# ESPBoard.net
KiCad netlist of a schematic drawn in Altium Designer
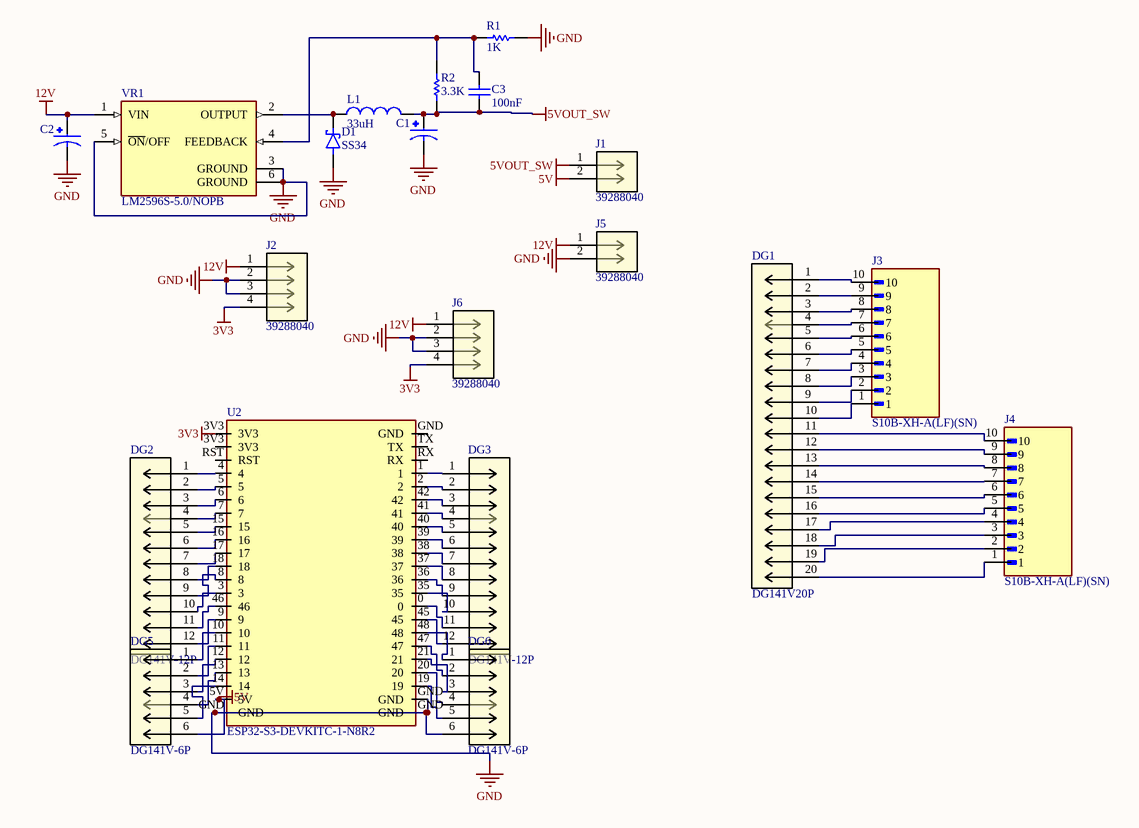
[diagram p0: ESPBoard.SchDoc]

(export (version "E")
  (design (tool "Eeschema 10.0.6"))
  (components
    (comp (ref "C1")
      (value "EEUFR1V101B")
      (footprint "220uF")
      (description "AL LYTIC, RADIAL, 35VDC, 100UF")
      (fields (field (name "MF") "Panasonic"))
      (libsource (lib "Schlib1") (part "EEUFR1V101B"))
    )
    (comp (ref "C2")
      (value "EEUFR1V101B")
      (footprint "100uF")
      (description "AL LYTIC, RADIAL, 35VDC, 100UF")
      (fields (field (name "MF") "Panasonic"))
      (libsource (lib "") (part "EEUFR1V101B_1"))
    )
    (comp (ref "C3")
      (value "100nF")
      (footprint "CAP0805R")
      (description "Capacitor")
      (libsource (lib "Simulation Generic Components") (part "Capacitor"))
    )
    (comp (ref "D1")
      (value "SS34")
      (footprint "DIOM7959X265N")
      (description "Diode Schottky 40 V 3A Surface Mount SMC (DO-214AB)")
      (fields (field (name "MF") "onsemi"))
      (libsource (lib "Schlib1") (part "SS34"))
    )
    (comp (ref "DG1")
      (value "DG141V20P")
      (footprint "141V-20P")
      (libsource (lib "Schlib1") (part "DG141V-20P"))
    )
    (comp (ref "DG2") (value "DG141V-12P") (footprint "141V-12P") (libsource (lib "") (part "DG141V-12P_1")))
    (comp (ref "DG3")
      (value "DG141V-12P")
      (footprint "141V-12P")
      (libsource (lib "Schlib1") (part "DG141V-12P"))
    )
    (comp (ref "DG5")
      (value "DG141V-6P")
      (footprint "141V-6P")
      (libsource (lib "Schlib1") (part "DG141V-6P"))
    )
    (comp (ref "DG6") (value "DG141V-6P") (footprint "141V-6P") (libsource (lib "") (part "DG141V-6P_1")))
    (comp (ref "J1")
      (value "39288040")
      (footprint "5566-02_MOL")
      (fields (field (name "COPYRIGHT") "Copyright (C) 2025 Ultra Librarian. All rights reserved."))
      (libsource (lib "Schlib1") (part "5566-02A"))
    )
    (comp (ref "J2")
      (value "39288040")
      (footprint "5566-04_MOL")
      (fields (field (name "COPYRIGHT") "Copyright (C) 2025 Ultra Librarian. All rights reserved."))
      (libsource (lib "Schlib1") (part "5566-04A"))
    )
    (comp (ref "J3")
      (value "S10B-XH-A(LF)(SN)")
      (footprint "JST_S10B-XH-A(LF)(SN)")
      (libsource (lib "Schlib1") (part "S10B-XH-A(LF)(SN)"))
    )
    (comp (ref "J4")
      (value "S10B-XH-A(LF)(SN)")
      (footprint "JST_S10B-XH-A(LF)(SN)")
      (libsource (lib "Schlib1") (part "S10B-XH-A(LF)(SN)"))
    )
    (comp (ref "J5")
      (value "39288040")
      (footprint "5566-02_MOL")
      (fields (field (name "COPYRIGHT") "Copyright (C) 2025 Ultra Librarian. All rights reserved."))
      (libsource (lib "Schlib1") (part "5566-02A"))
    )
    (comp (ref "J6")
      (value "39288040")
      (footprint "5566-04_MOL")
      (fields (field (name "COPYRIGHT") "Copyright (C) 2025 Ultra Librarian. All rights reserved."))
      (libsource (lib "Schlib1") (part "5566-04A"))
    )
    (comp (ref "L1")
      (value "33uH")
      (footprint "SC1280S-33uH")
      (description "Inductor")
      (libsource (lib "Simulation Generic Components") (part "Inductor"))
    )
    (comp (ref "R1")
      (value "1K")
      (footprint "RES0805W")
      (description "Resistor")
      (libsource (lib "Simulation Generic Components") (part "Resistor"))
    )
    (comp (ref "R2")
      (value "3.3K")
      (footprint "RES0805W")
      (description "Resistor")
      (libsource (lib "Simulation Generic Components") (part "Resistor"))
    )
    (comp (ref "U2")
      (value "ESP32-S3-DEVKITC-1-N8R2")
      (footprint "ESP32-S3-DEVKITC-1")
      (fields (field (name "MF") "Espressif Systems"))
      (libsource (lib "Schlib1") (part "ESP32-S3-DEVKITC-1-N8R2"))
    )
    (comp (ref "VR1")
      (value "LM2596S-5.0/NOPB")
      (footprint "VREG_LM2596S-5.0/NOPB")
      (description "SIMPLE SWITCHERÂ® 4.5V to 40V, 3A Low Component Count Step-Down Regulator 5-DDPAK/TO-263")
      (fields (field (name "MF") "Texas Instruments") (field (name "MP") "LM2596S-5.0"))
      (libsource (lib "Schlib1") (part "LM2596S-5.0/NOPB"))
    )
  )
  (nets
    (net (code "1") (name "3V3") (class "Default")
      (node (ref "J2") (pin "4") (pinfunction "4_4") (pintype "passive"))
      (node (ref "J6") (pin "4") (pinfunction "4_4") (pintype "passive"))
      (node (ref "U2") (pin "3V3") (pinfunction "3V3_3V3") (pintype "passive"))
    )
    (net (code "2") (name "5V") (class "Default")
      (node (ref "DG5") (pin "6") (pinfunction "6_6") (pintype "passive"))
      (node (ref "J1") (pin "2") (pinfunction "2_2") (pintype "passive"))
      (node (ref "U2") (pin "5V") (pinfunction "5V_5V") (pintype "passive"))
    )
    (net (code "3") (name "5VOUT_SW") (class "Default")
      (node (ref "C1") (pin "P") (pinfunction "P_P") (pintype "passive"))
      (node (ref "C3") (pin "1") (pinfunction "1_1") (pintype "passive"))
      (node (ref "J1") (pin "1") (pinfunction "1_1") (pintype "passive"))
      (node (ref "L1") (pin "2") (pinfunction "2_2") (pintype "passive"))
      (node (ref "R2") (pin "1") (pinfunction "1_1") (pintype "passive"))
    )
    (net (code "4") (name "12V") (class "Default")
      (node (ref "C2") (pin "P") (pinfunction "P_P") (pintype "passive"))
      (node (ref "J2") (pin "1") (pinfunction "1_1") (pintype "passive"))
      (node (ref "J5") (pin "1") (pinfunction "1_1") (pintype "passive"))
      (node (ref "J6") (pin "1") (pinfunction "1_1") (pintype "passive"))
      (node (ref "VR1") (pin "1") (pinfunction "VIN_1") (pintype "input"))
    )
    (net (code "5") (name "GND") (class "Default")
      (node (ref "C1") (pin "N") (pinfunction "N_N") (pintype "passive"))
      (node (ref "C2") (pin "N") (pinfunction "N_N") (pintype "passive"))
      (node (ref "D1") (pin "A") (pinfunction "A_A") (pintype "passive"))
      (node (ref "DG6") (pin "6") (pinfunction "6_6") (pintype "passive"))
      (node (ref "J2") (pin "2") (pinfunction "2_2") (pintype "passive"))
      (node (ref "J2") (pin "3") (pinfunction "3_3") (pintype "passive"))
      (node (ref "J5") (pin "2") (pinfunction "2_2") (pintype "passive"))
      (node (ref "J6") (pin "2") (pinfunction "2_2") (pintype "passive"))
      (node (ref "J6") (pin "3") (pinfunction "3_3") (pintype "passive"))
      (node (ref "R1") (pin "1") (pinfunction "1_1") (pintype "passive"))
      (node (ref "U2") (pin "GND") (pinfunction "GND_GND") (pintype "passive"))
      (node (ref "VR1") (pin "3") (pinfunction "GROUND_3") (pintype "power_in"))
      (node (ref "VR1") (pin "5") (pinfunction "~{ON}/OFF_5") (pintype "input"))
      (node (ref "VR1") (pin "6") (pinfunction "GROUND_6") (pintype "power_in"))
    )
    (net (code "6") (name "Net-(D1-K)") (class "Default")
      (node (ref "D1") (pin "C") (pinfunction "K_C") (pintype "passive"))
      (node (ref "L1") (pin "1") (pinfunction "1_1") (pintype "passive"))
      (node (ref "VR1") (pin "2") (pinfunction "OUTPUT_2") (pintype "output"))
    )
    (net (code "7") (name "Net-(DG1-Pad1)") (class "Default")
      (node (ref "DG1") (pin "1") (pinfunction "1_1") (pintype "passive"))
      (node (ref "J3") (pin "10") (pinfunction "10_10") (pintype "passive"))
    )
    (net (code "8") (name "Net-(DG1-Pad2)") (class "Default")
      (node (ref "DG1") (pin "2") (pinfunction "2_2") (pintype "passive"))
      (node (ref "J3") (pin "9") (pinfunction "9_9") (pintype "passive"))
    )
    (net (code "9") (name "Net-(DG1-Pad3)") (class "Default")
      (node (ref "DG1") (pin "3") (pinfunction "3_3") (pintype "passive"))
      (node (ref "J3") (pin "8") (pinfunction "8_8") (pintype "passive"))
    )
    (net (code "10") (name "Net-(DG1-Pad4)") (class "Default")
      (node (ref "DG1") (pin "4") (pinfunction "4_4") (pintype "passive"))
      (node (ref "J3") (pin "7") (pinfunction "7_7") (pintype "passive"))
    )
    (net (code "11") (name "Net-(DG1-Pad5)") (class "Default")
      (node (ref "DG1") (pin "5") (pinfunction "5_5") (pintype "passive"))
      (node (ref "J3") (pin "6") (pinfunction "6_6") (pintype "passive"))
    )
    (net (code "12") (name "Net-(DG1-Pad6)") (class "Default")
      (node (ref "DG1") (pin "6") (pinfunction "6_6") (pintype "passive"))
      (node (ref "J3") (pin "5") (pinfunction "5_5") (pintype "passive"))
    )
    (net (code "13") (name "Net-(DG1-Pad7)") (class "Default")
      (node (ref "DG1") (pin "7") (pinfunction "7_7") (pintype "passive"))
      (node (ref "J3") (pin "4") (pinfunction "4_4") (pintype "passive"))
    )
    (net (code "14") (name "Net-(DG1-Pad8)") (class "Default")
      (node (ref "DG1") (pin "8") (pinfunction "8_8") (pintype "passive"))
      (node (ref "J3") (pin "3") (pinfunction "3_3") (pintype "passive"))
    )
    (net (code "15") (name "Net-(DG1-Pad9)") (class "Default")
      (node (ref "DG1") (pin "9") (pinfunction "9_9") (pintype "passive"))
      (node (ref "J3") (pin "2") (pinfunction "2_2") (pintype "passive"))
    )
    (net (code "16") (name "Net-(DG1-Pad10)") (class "Default")
      (node (ref "DG1") (pin "10") (pinfunction "10_10") (pintype "passive"))
      (node (ref "J3") (pin "1") (pinfunction "1_1") (pintype "passive"))
    )
    (net (code "17") (name "Net-(DG1-Pad11)") (class "Default")
      (node (ref "DG1") (pin "11") (pinfunction "11_11") (pintype "passive"))
      (node (ref "J4") (pin "10") (pinfunction "10_10") (pintype "passive"))
    )
    (net (code "18") (name "Net-(DG1-Pad12)") (class "Default")
      (node (ref "DG1") (pin "12") (pinfunction "12_12") (pintype "passive"))
      (node (ref "J4") (pin "9") (pinfunction "9_9") (pintype "passive"))
    )
    (net (code "19") (name "Net-(DG1-Pad13)") (class "Default")
      (node (ref "DG1") (pin "13") (pinfunction "13_13") (pintype "passive"))
      (node (ref "J4") (pin "8") (pinfunction "8_8") (pintype "passive"))
    )
    (net (code "20") (name "Net-(DG1-Pad14)") (class "Default")
      (node (ref "DG1") (pin "14") (pinfunction "14_14") (pintype "passive"))
      (node (ref "J4") (pin "7") (pinfunction "7_7") (pintype "passive"))
    )
    (net (code "21") (name "Net-(DG1-Pad15)") (class "Default")
      (node (ref "DG1") (pin "15") (pinfunction "15_15") (pintype "passive"))
      (node (ref "J4") (pin "6") (pinfunction "6_6") (pintype "passive"))
    )
    (net (code "22") (name "Net-(DG1-Pad16)") (class "Default")
      (node (ref "DG1") (pin "16") (pinfunction "16_16") (pintype "passive"))
      (node (ref "J4") (pin "5") (pinfunction "5_5") (pintype "passive"))
    )
    (net (code "23") (name "Net-(DG1-Pad17)") (class "Default")
      (node (ref "DG1") (pin "17") (pinfunction "17_17") (pintype "passive"))
      (node (ref "J4") (pin "4") (pinfunction "4_4") (pintype "passive"))
    )
    (net (code "24") (name "Net-(DG1-Pad18)") (class "Default")
      (node (ref "DG1") (pin "18") (pinfunction "18_18") (pintype "passive"))
      (node (ref "J4") (pin "3") (pinfunction "3_3") (pintype "passive"))
    )
    (net (code "25") (name "Net-(DG1-Pad19)") (class "Default")
      (node (ref "DG1") (pin "19") (pinfunction "19_19") (pintype "passive"))
      (node (ref "J4") (pin "2") (pinfunction "2_2") (pintype "passive"))
    )
    (net (code "26") (name "Net-(DG1-Pad20)") (class "Default")
      (node (ref "DG1") (pin "20") (pinfunction "20_20") (pintype "passive"))
      (node (ref "J4") (pin "1") (pinfunction "1_1") (pintype "passive"))
    )
    (net (code "27") (name "Net-(DG2-Pad1)") (class "Default")
      (node (ref "DG2") (pin "1") (pinfunction "1_1") (pintype "passive"))
      (node (ref "U2") (pin "4") (pinfunction "4_4") (pintype "passive"))
    )
    (net (code "28") (name "Net-(DG2-Pad2)") (class "Default")
      (node (ref "DG2") (pin "2") (pinfunction "2_2") (pintype "passive"))
      (node (ref "U2") (pin "5") (pinfunction "5_5") (pintype "passive"))
    )
    (net (code "29") (name "Net-(DG2-Pad3)") (class "Default")
      (node (ref "DG2") (pin "3") (pinfunction "3_3") (pintype "passive"))
      (node (ref "U2") (pin "6") (pinfunction "6_6") (pintype "passive"))
    )
    (net (code "30") (name "Net-(DG2-Pad4)") (class "Default")
      (node (ref "DG2") (pin "4") (pinfunction "4_4") (pintype "passive"))
      (node (ref "U2") (pin "7") (pinfunction "7_7") (pintype "passive"))
    )
    (net (code "31") (name "Net-(DG2-Pad5)") (class "Default")
      (node (ref "DG2") (pin "5") (pinfunction "5_5") (pintype "passive"))
      (node (ref "U2") (pin "15") (pinfunction "15_15") (pintype "passive"))
    )
    (net (code "32") (name "Net-(DG2-Pad6)") (class "Default")
      (node (ref "DG2") (pin "6") (pinfunction "6_6") (pintype "passive"))
      (node (ref "U2") (pin "16") (pinfunction "16_16") (pintype "passive"))
    )
    (net (code "33") (name "Net-(DG2-Pad7)") (class "Default")
      (node (ref "DG2") (pin "7") (pinfunction "7_7") (pintype "passive"))
      (node (ref "U2") (pin "17") (pinfunction "17_17") (pintype "passive"))
    )
    (net (code "34") (name "Net-(DG2-Pad8)") (class "Default")
      (node (ref "DG2") (pin "8") (pinfunction "8_8") (pintype "passive"))
      (node (ref "U2") (pin "18") (pinfunction "18_18") (pintype "passive"))
    )
    (net (code "35") (name "Net-(DG2-Pad9)") (class "Default")
      (node (ref "DG2") (pin "9") (pinfunction "9_9") (pintype "passive"))
      (node (ref "U2") (pin "8") (pinfunction "8_8") (pintype "passive"))
    )
    (net (code "36") (name "Net-(DG2-Pad10)") (class "Default")
      (node (ref "DG2") (pin "10") (pinfunction "10_10") (pintype "passive"))
      (node (ref "U2") (pin "3") (pinfunction "3_3") (pintype "passive"))
    )
    (net (code "37") (name "Net-(DG2-Pad11)") (class "Default")
      (node (ref "DG2") (pin "11") (pinfunction "11_11") (pintype "passive"))
      (node (ref "U2") (pin "46") (pinfunction "46_46") (pintype "passive"))
    )
    (net (code "38") (name "Net-(DG2-Pad12)") (class "Default")
      (node (ref "DG2") (pin "12") (pinfunction "12_12") (pintype "passive"))
      (node (ref "U2") (pin "9") (pinfunction "9_9") (pintype "passive"))
    )
    (net (code "39") (name "Net-(DG3-Pad1)") (class "Default")
      (node (ref "DG3") (pin "1") (pinfunction "1_1") (pintype "passive"))
      (node (ref "U2") (pin "1") (pinfunction "1_1") (pintype "passive"))
    )
    (net (code "40") (name "Net-(DG3-Pad2)") (class "Default")
      (node (ref "DG3") (pin "2") (pinfunction "2_2") (pintype "passive"))
      (node (ref "U2") (pin "2") (pinfunction "2_2") (pintype "passive"))
    )
    (net (code "41") (name "Net-(DG3-Pad3)") (class "Default")
      (node (ref "DG3") (pin "3") (pinfunction "3_3") (pintype "passive"))
      (node (ref "U2") (pin "42") (pinfunction "42_42") (pintype "passive"))
    )
    (net (code "42") (name "Net-(DG3-Pad4)") (class "Default")
      (node (ref "DG3") (pin "4") (pinfunction "4_4") (pintype "passive"))
      (node (ref "U2") (pin "41") (pinfunction "41_41") (pintype "passive"))
    )
    (net (code "43") (name "Net-(DG3-Pad5)") (class "Default")
      (node (ref "DG3") (pin "5") (pinfunction "5_5") (pintype "passive"))
      (node (ref "U2") (pin "40") (pinfunction "40_40") (pintype "passive"))
    )
    (net (code "44") (name "Net-(DG3-Pad6)") (class "Default")
      (node (ref "DG3") (pin "6") (pinfunction "6_6") (pintype "passive"))
      (node (ref "U2") (pin "39") (pinfunction "39_39") (pintype "passive"))
    )
    (net (code "45") (name "Net-(DG3-Pad7)") (class "Default")
      (node (ref "DG3") (pin "7") (pinfunction "7_7") (pintype "passive"))
      (node (ref "U2") (pin "38") (pinfunction "38_38") (pintype "passive"))
    )
    (net (code "46") (name "Net-(DG3-Pad8)") (class "Default")
      (node (ref "DG3") (pin "8") (pinfunction "8_8") (pintype "passive"))
      (node (ref "U2") (pin "37") (pinfunction "37_37") (pintype "passive"))
    )
    (net (code "47") (name "Net-(DG3-Pad9)") (class "Default")
      (node (ref "DG3") (pin "9") (pinfunction "9_9") (pintype "passive"))
      (node (ref "U2") (pin "36") (pinfunction "36_36") (pintype "passive"))
    )
    (net (code "48") (name "Net-(DG3-Pad10)") (class "Default")
      (node (ref "DG3") (pin "10") (pinfunction "10_10") (pintype "passive"))
      (node (ref "U2") (pin "35") (pinfunction "35_35") (pintype "passive"))
    )
    (net (code "49") (name "Net-(DG3-Pad11)") (class "Default")
      (node (ref "DG3") (pin "11") (pinfunction "11_11") (pintype "passive"))
      (node (ref "U2") (pin "0") (pinfunction "0_0") (pintype "passive"))
    )
    (net (code "50") (name "Net-(DG3-Pad12)") (class "Default")
      (node (ref "DG3") (pin "12") (pinfunction "12_12") (pintype "passive"))
      (node (ref "U2") (pin "45") (pinfunction "45_45") (pintype "passive"))
    )
    (net (code "51") (name "Net-(DG5-Pad1)") (class "Default")
      (node (ref "DG5") (pin "1") (pinfunction "1_1") (pintype "passive"))
      (node (ref "U2") (pin "10") (pinfunction "10_10") (pintype "passive"))
    )
    (net (code "52") (name "Net-(DG5-Pad2)") (class "Default")
      (node (ref "DG5") (pin "2") (pinfunction "2_2") (pintype "passive"))
      (node (ref "U2") (pin "11") (pinfunction "11_11") (pintype "passive"))
    )
    (net (code "53") (name "Net-(DG5-Pad3)") (class "Default")
      (node (ref "DG5") (pin "3") (pinfunction "3_3") (pintype "passive"))
      (node (ref "U2") (pin "12") (pinfunction "12_12") (pintype "passive"))
    )
    (net (code "54") (name "Net-(DG5-Pad4)") (class "Default")
      (node (ref "DG5") (pin "4") (pinfunction "4_4") (pintype "passive"))
      (node (ref "U2") (pin "13") (pinfunction "13_13") (pintype "passive"))
    )
    (net (code "55") (name "Net-(DG5-Pad5)") (class "Default")
      (node (ref "DG5") (pin "5") (pinfunction "5_5") (pintype "passive"))
      (node (ref "U2") (pin "14") (pinfunction "14_14") (pintype "passive"))
    )
    (net (code "56") (name "Net-(DG6-Pad1)") (class "Default")
      (node (ref "DG6") (pin "1") (pinfunction "1_1") (pintype "passive"))
      (node (ref "U2") (pin "48") (pinfunction "48_48") (pintype "passive"))
    )
    (net (code "57") (name "Net-(DG6-Pad2)") (class "Default")
      (node (ref "DG6") (pin "2") (pinfunction "2_2") (pintype "passive"))
      (node (ref "U2") (pin "47") (pinfunction "47_47") (pintype "passive"))
    )
    (net (code "58") (name "Net-(DG6-Pad3)") (class "Default")
      (node (ref "DG6") (pin "3") (pinfunction "3_3") (pintype "passive"))
      (node (ref "U2") (pin "21") (pinfunction "21_21") (pintype "passive"))
    )
    (net (code "59") (name "Net-(DG6-Pad4)") (class "Default")
      (node (ref "DG6") (pin "4") (pinfunction "4_4") (pintype "passive"))
      (node (ref "U2") (pin "20") (pinfunction "20_20") (pintype "passive"))
    )
    (net (code "60") (name "Net-(DG6-Pad5)") (class "Default")
      (node (ref "DG6") (pin "5") (pinfunction "5_5") (pintype "passive"))
      (node (ref "U2") (pin "19") (pinfunction "19_19") (pintype "passive"))
    )
    (net (code "61") (name "Net-(VR1-FEEDBACK)") (class "Default")
      (node (ref "C3") (pin "2") (pinfunction "2_2") (pintype "passive"))
      (node (ref "R1") (pin "2") (pinfunction "2_2") (pintype "passive"))
      (node (ref "R2") (pin "2") (pinfunction "2_2") (pintype "passive"))
      (node (ref "VR1") (pin "4") (pinfunction "FEEDBACK_4") (pintype "input"))
    )
    (net (code "62") (name "unconnected-(U2-Pad3V3)") (class "Default")
      (node (ref "U2") (pin "3V3") (pinfunction "3V3_3V3") (pintype "passive"))
    )
    (net (code "63") (name "unconnected-(U2-PadGND)") (class "Default")
      (node (ref "U2") (pin "GND") (pinfunction "GND_GND") (pintype "passive"))
    )
    (net (code "64") (name "unconnected-(U2-PadRST)") (class "Default")
      (node (ref "U2") (pin "RST") (pinfunction "RST_RST") (pintype "passive"))
    )
    (net (code "65") (name "unconnected-(U2-PadRX)") (class "Default")
      (node (ref "U2") (pin "RX") (pinfunction "RX_RX") (pintype "passive"))
    )
    (net (code "66") (name "unconnected-(U2-PadTX)") (class "Default")
      (node (ref "U2") (pin "TX") (pinfunction "TX_TX") (pintype "passive"))
    )
  )
)
